# BMS_AFE_-_Cell_Inputs.net
KiCad netlist of a schematic drawn in Altium Designer
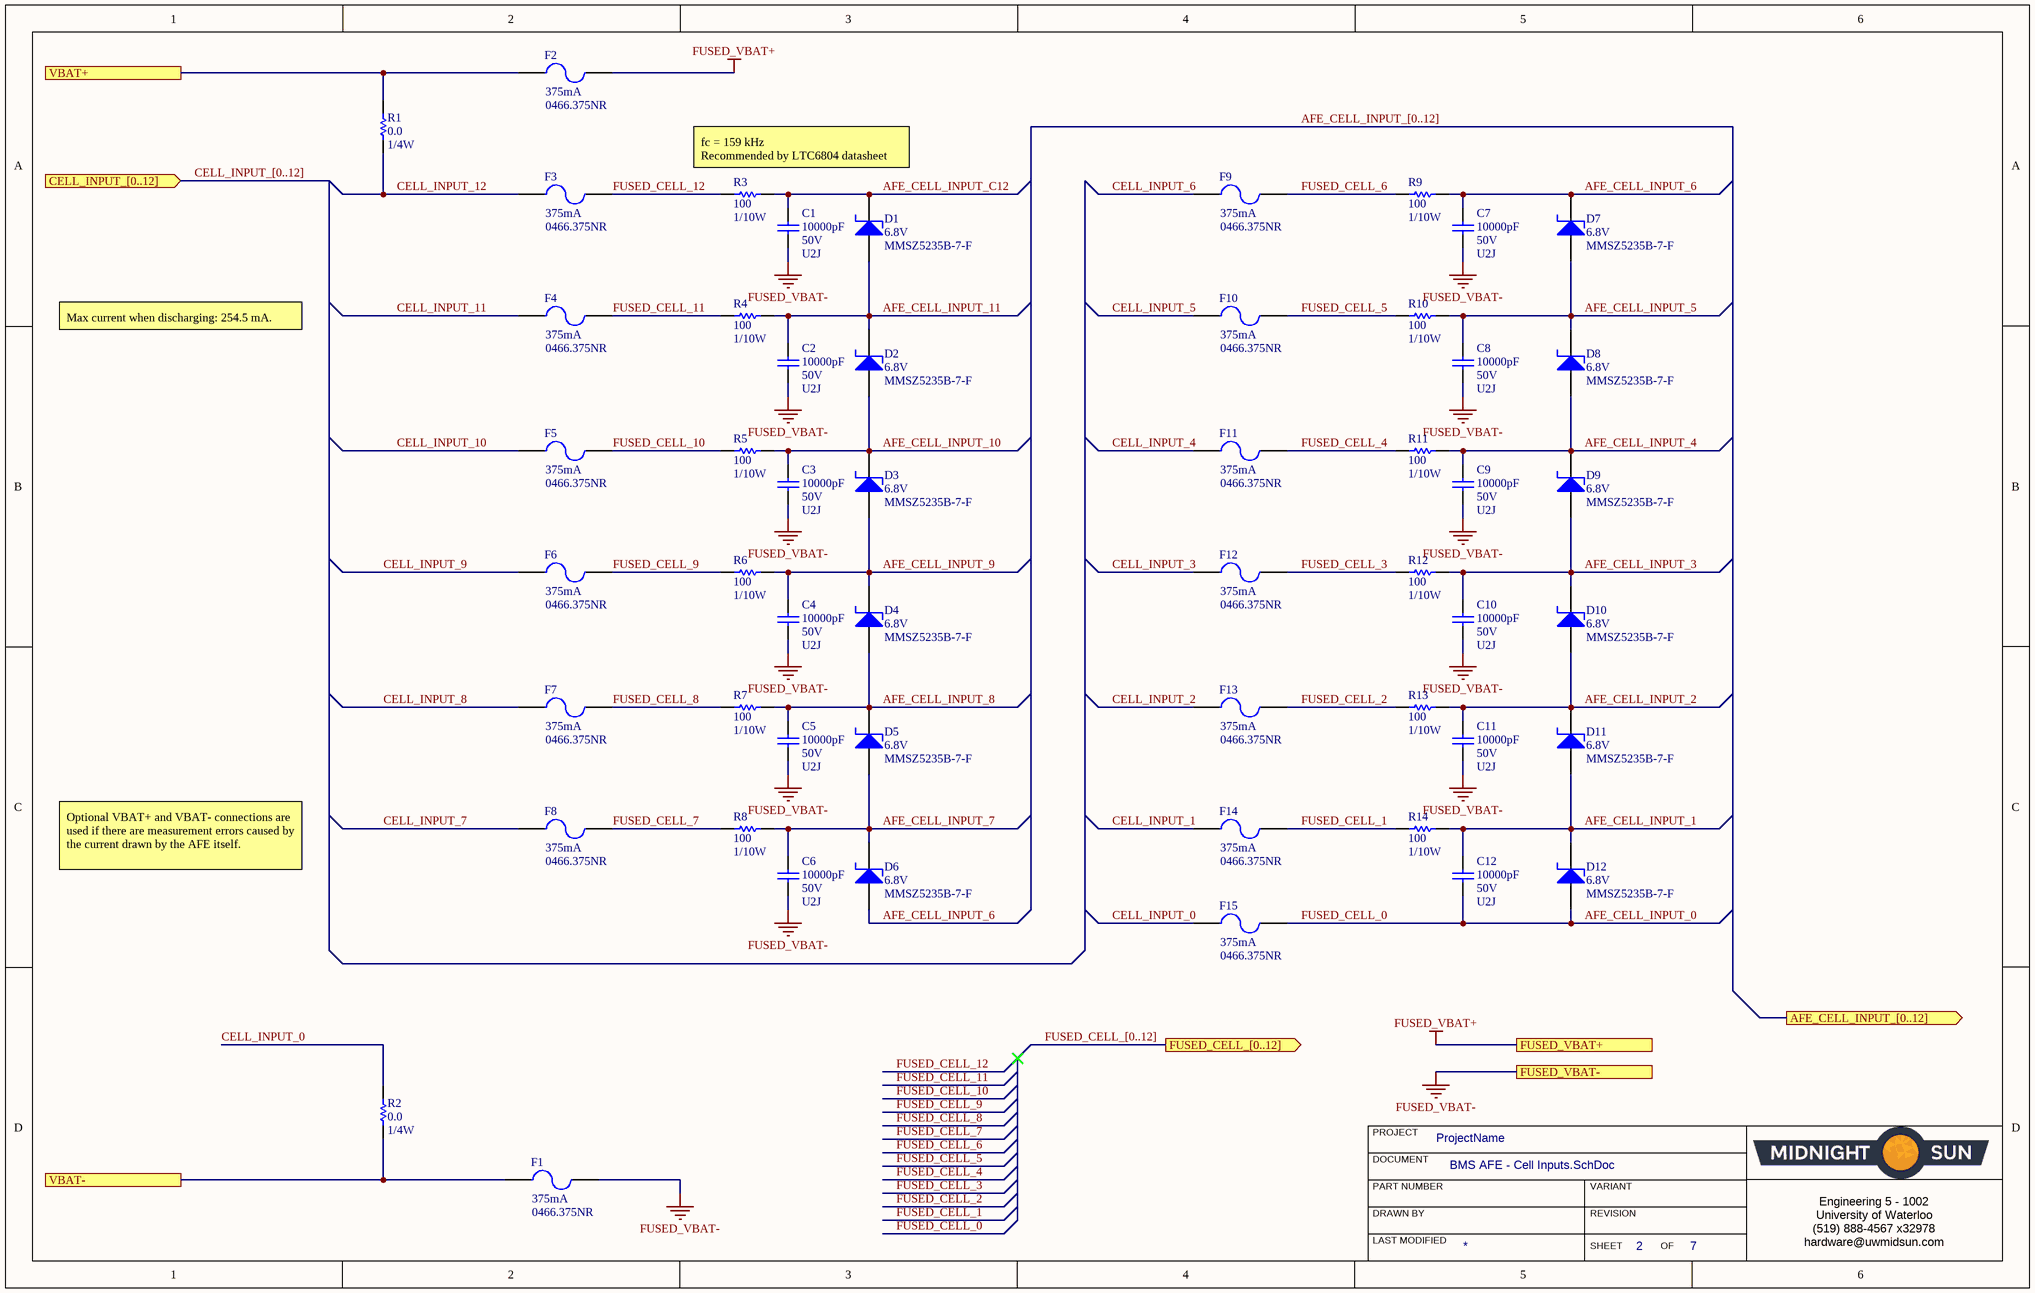
[diagram p0: BMS AFE - Cell Inputs.SchDoc]

(export (version "E")
  (design (tool "Eeschema 10.0.6"))
  (components
    (comp (ref "C1")
      (value "CAP CER 10nF 50V 5% X7R 0603")
      (footprint "CAP, 0603")
      (description "10000pF ±5% 50V Ceramic Capacitor U2J 0603 (1608 Metric)")
      (fields
        (field (name "TOLERANCE") "±5%")
        (field (name "CAPACITANCE") "10000pF")
        (field (name "VOLTAGE") "50V")
        (field (name "TEMPERATURE COEFFICIENT") "U2J")
      )
      (libsource (lib "Schematic Diagrams") (part "CAP CER 10nF 50V 5% X7R 0603"))
    )
    (comp (ref "C2")
      (value "CAP CER 10nF 50V 5% X7R 0603")
      (footprint "CAP, 0603")
      (description "10000pF ±5% 50V Ceramic Capacitor U2J 0603 (1608 Metric)")
      (fields
        (field (name "TOLERANCE") "±5%")
        (field (name "CAPACITANCE") "10000pF")
        (field (name "VOLTAGE") "50V")
        (field (name "TEMPERATURE COEFFICIENT") "U2J")
      )
      (libsource (lib "Schematic Diagrams") (part "CAP CER 10nF 50V 5% X7R 0603"))
    )
    (comp (ref "C3")
      (value "CAP CER 10nF 50V 5% X7R 0603")
      (footprint "CAP, 0603")
      (description "10000pF ±5% 50V Ceramic Capacitor U2J 0603 (1608 Metric)")
      (fields
        (field (name "TOLERANCE") "±5%")
        (field (name "CAPACITANCE") "10000pF")
        (field (name "VOLTAGE") "50V")
        (field (name "TEMPERATURE COEFFICIENT") "U2J")
      )
      (libsource (lib "Schematic Diagrams") (part "CAP CER 10nF 50V 5% X7R 0603"))
    )
    (comp (ref "C4")
      (value "CAP CER 10nF 50V 5% X7R 0603")
      (footprint "CAP, 0603")
      (description "10000pF ±5% 50V Ceramic Capacitor U2J 0603 (1608 Metric)")
      (fields
        (field (name "TOLERANCE") "±5%")
        (field (name "CAPACITANCE") "10000pF")
        (field (name "VOLTAGE") "50V")
        (field (name "TEMPERATURE COEFFICIENT") "U2J")
      )
      (libsource (lib "Schematic Diagrams") (part "CAP CER 10nF 50V 5% X7R 0603"))
    )
    (comp (ref "C5")
      (value "CAP CER 10nF 50V 5% X7R 0603")
      (footprint "CAP, 0603")
      (description "10000pF ±5% 50V Ceramic Capacitor U2J 0603 (1608 Metric)")
      (fields
        (field (name "TOLERANCE") "±5%")
        (field (name "CAPACITANCE") "10000pF")
        (field (name "VOLTAGE") "50V")
        (field (name "TEMPERATURE COEFFICIENT") "U2J")
      )
      (libsource (lib "Schematic Diagrams") (part "CAP CER 10nF 50V 5% X7R 0603"))
    )
    (comp (ref "C6")
      (value "CAP CER 10nF 50V 5% X7R 0603")
      (footprint "CAP, 0603")
      (description "10000pF ±5% 50V Ceramic Capacitor U2J 0603 (1608 Metric)")
      (fields
        (field (name "TOLERANCE") "±5%")
        (field (name "CAPACITANCE") "10000pF")
        (field (name "VOLTAGE") "50V")
        (field (name "TEMPERATURE COEFFICIENT") "U2J")
      )
      (libsource (lib "Schematic Diagrams") (part "CAP CER 10nF 50V 5% X7R 0603"))
    )
    (comp (ref "C7")
      (value "CAP CER 10nF 50V 5% X7R 0603")
      (footprint "CAP, 0603")
      (description "10000pF ±5% 50V Ceramic Capacitor U2J 0603 (1608 Metric)")
      (fields
        (field (name "TOLERANCE") "±5%")
        (field (name "CAPACITANCE") "10000pF")
        (field (name "VOLTAGE") "50V")
        (field (name "TEMPERATURE COEFFICIENT") "U2J")
      )
      (libsource (lib "Schematic Diagrams") (part "CAP CER 10nF 50V 5% X7R 0603"))
    )
    (comp (ref "C8")
      (value "CAP CER 10nF 50V 5% X7R 0603")
      (footprint "CAP, 0603")
      (description "10000pF ±5% 50V Ceramic Capacitor U2J 0603 (1608 Metric)")
      (fields
        (field (name "TOLERANCE") "±5%")
        (field (name "CAPACITANCE") "10000pF")
        (field (name "VOLTAGE") "50V")
        (field (name "TEMPERATURE COEFFICIENT") "U2J")
      )
      (libsource (lib "Schematic Diagrams") (part "CAP CER 10nF 50V 5% X7R 0603"))
    )
    (comp (ref "C9")
      (value "CAP CER 10nF 50V 5% X7R 0603")
      (footprint "CAP, 0603")
      (description "10000pF ±5% 50V Ceramic Capacitor U2J 0603 (1608 Metric)")
      (fields
        (field (name "TOLERANCE") "±5%")
        (field (name "CAPACITANCE") "10000pF")
        (field (name "VOLTAGE") "50V")
        (field (name "TEMPERATURE COEFFICIENT") "U2J")
      )
      (libsource (lib "Schematic Diagrams") (part "CAP CER 10nF 50V 5% X7R 0603"))
    )
    (comp (ref "C10")
      (value "CAP CER 10nF 50V 5% X7R 0603")
      (footprint "CAP, 0603")
      (description "10000pF ±5% 50V Ceramic Capacitor U2J 0603 (1608 Metric)")
      (fields
        (field (name "TOLERANCE") "±5%")
        (field (name "CAPACITANCE") "10000pF")
        (field (name "VOLTAGE") "50V")
        (field (name "TEMPERATURE COEFFICIENT") "U2J")
      )
      (libsource (lib "Schematic Diagrams") (part "CAP CER 10nF 50V 5% X7R 0603"))
    )
    (comp (ref "C11")
      (value "CAP CER 10nF 50V 5% X7R 0603")
      (footprint "CAP, 0603")
      (description "10000pF ±5% 50V Ceramic Capacitor U2J 0603 (1608 Metric)")
      (fields
        (field (name "TOLERANCE") "±5%")
        (field (name "CAPACITANCE") "10000pF")
        (field (name "VOLTAGE") "50V")
        (field (name "TEMPERATURE COEFFICIENT") "U2J")
      )
      (libsource (lib "Schematic Diagrams") (part "CAP CER 10nF 50V 5% X7R 0603"))
    )
    (comp (ref "C12")
      (value "CAP CER 10nF 50V 5% X7R 0603")
      (footprint "CAP, 0603")
      (description "10000pF ±5% 50V Ceramic Capacitor U2J 0603 (1608 Metric)")
      (fields
        (field (name "TOLERANCE") "±5%")
        (field (name "CAPACITANCE") "10000pF")
        (field (name "VOLTAGE") "50V")
        (field (name "TEMPERATURE COEFFICIENT") "U2J")
      )
      (libsource (lib "Schematic Diagrams") (part "CAP CER 10nF 50V 5% X7R 0603"))
    )
    (comp (ref "D1")
      (value "6.8V")
      (footprint "DIODE SOD123")
      (description "Zener Diode 6.8V 500mW ±5% Surface Mount SOD-123")
      (fields
        (field (name "MANUFACTURER") "Diodes Incorporated")
        (field (name "TOLERANCE") "±5%")
        (field (name "MANUFACTURER PART NUMBER") "MMSZ5235B-7-F")
      )
      (libsource (lib "Schematic Diagrams") (part "DIODE ZENER 6.8V 500MW SOD123"))
    )
    (comp (ref "D2")
      (value "6.8V")
      (footprint "DIODE SOD123")
      (description "Zener Diode 6.8V 500mW ±5% Surface Mount SOD-123")
      (fields
        (field (name "MANUFACTURER") "Diodes Incorporated")
        (field (name "TOLERANCE") "±5%")
        (field (name "MANUFACTURER PART NUMBER") "MMSZ5235B-7-F")
      )
      (libsource (lib "Schematic Diagrams") (part "DIODE ZENER 6.8V 500MW SOD123"))
    )
    (comp (ref "D3")
      (value "6.8V")
      (footprint "DIODE SOD123")
      (description "Zener Diode 6.8V 500mW ±5% Surface Mount SOD-123")
      (fields
        (field (name "MANUFACTURER") "Diodes Incorporated")
        (field (name "TOLERANCE") "±5%")
        (field (name "MANUFACTURER PART NUMBER") "MMSZ5235B-7-F")
      )
      (libsource (lib "Schematic Diagrams") (part "DIODE ZENER 6.8V 500MW SOD123"))
    )
    (comp (ref "D4")
      (value "6.8V")
      (footprint "DIODE SOD123")
      (description "Zener Diode 6.8V 500mW ±5% Surface Mount SOD-123")
      (fields
        (field (name "MANUFACTURER") "Diodes Incorporated")
        (field (name "TOLERANCE") "±5%")
        (field (name "MANUFACTURER PART NUMBER") "MMSZ5235B-7-F")
      )
      (libsource (lib "Schematic Diagrams") (part "DIODE ZENER 6.8V 500MW SOD123"))
    )
    (comp (ref "D5")
      (value "6.8V")
      (footprint "DIODE SOD123")
      (description "Zener Diode 6.8V 500mW ±5% Surface Mount SOD-123")
      (fields
        (field (name "MANUFACTURER") "Diodes Incorporated")
        (field (name "TOLERANCE") "±5%")
        (field (name "MANUFACTURER PART NUMBER") "MMSZ5235B-7-F")
      )
      (libsource (lib "Schematic Diagrams") (part "DIODE ZENER 6.8V 500MW SOD123"))
    )
    (comp (ref "D6")
      (value "6.8V")
      (footprint "DIODE SOD123")
      (description "Zener Diode 6.8V 500mW ±5% Surface Mount SOD-123")
      (fields
        (field (name "MANUFACTURER") "Diodes Incorporated")
        (field (name "TOLERANCE") "±5%")
        (field (name "MANUFACTURER PART NUMBER") "MMSZ5235B-7-F")
      )
      (libsource (lib "Schematic Diagrams") (part "DIODE ZENER 6.8V 500MW SOD123"))
    )
    (comp (ref "D7")
      (value "6.8V")
      (footprint "DIODE SOD123")
      (description "Zener Diode 6.8V 500mW ±5% Surface Mount SOD-123")
      (fields
        (field (name "MANUFACTURER") "Diodes Incorporated")
        (field (name "TOLERANCE") "±5%")
        (field (name "MANUFACTURER PART NUMBER") "MMSZ5235B-7-F")
      )
      (libsource (lib "Schematic Diagrams") (part "DIODE ZENER 6.8V 500MW SOD123"))
    )
    (comp (ref "D8")
      (value "6.8V")
      (footprint "DIODE SOD123")
      (description "Zener Diode 6.8V 500mW ±5% Surface Mount SOD-123")
      (fields
        (field (name "MANUFACTURER") "Diodes Incorporated")
        (field (name "TOLERANCE") "±5%")
        (field (name "MANUFACTURER PART NUMBER") "MMSZ5235B-7-F")
      )
      (libsource (lib "Schematic Diagrams") (part "DIODE ZENER 6.8V 500MW SOD123"))
    )
    (comp (ref "D9")
      (value "6.8V")
      (footprint "DIODE SOD123")
      (description "Zener Diode 6.8V 500mW ±5% Surface Mount SOD-123")
      (fields
        (field (name "MANUFACTURER") "Diodes Incorporated")
        (field (name "TOLERANCE") "±5%")
        (field (name "MANUFACTURER PART NUMBER") "MMSZ5235B-7-F")
      )
      (libsource (lib "Schematic Diagrams") (part "DIODE ZENER 6.8V 500MW SOD123"))
    )
    (comp (ref "D10")
      (value "6.8V")
      (footprint "DIODE SOD123")
      (description "Zener Diode 6.8V 500mW ±5% Surface Mount SOD-123")
      (fields
        (field (name "MANUFACTURER") "Diodes Incorporated")
        (field (name "TOLERANCE") "±5%")
        (field (name "MANUFACTURER PART NUMBER") "MMSZ5235B-7-F")
      )
      (libsource (lib "Schematic Diagrams") (part "DIODE ZENER 6.8V 500MW SOD123"))
    )
    (comp (ref "D11")
      (value "6.8V")
      (footprint "DIODE SOD123")
      (description "Zener Diode 6.8V 500mW ±5% Surface Mount SOD-123")
      (fields
        (field (name "MANUFACTURER") "Diodes Incorporated")
        (field (name "TOLERANCE") "±5%")
        (field (name "MANUFACTURER PART NUMBER") "MMSZ5235B-7-F")
      )
      (libsource (lib "Schematic Diagrams") (part "DIODE ZENER 6.8V 500MW SOD123"))
    )
    (comp (ref "D12")
      (value "6.8V")
      (footprint "DIODE SOD123")
      (description "Zener Diode 6.8V 500mW ±5% Surface Mount SOD-123")
      (fields
        (field (name "MANUFACTURER") "Diodes Incorporated")
        (field (name "TOLERANCE") "±5%")
        (field (name "MANUFACTURER PART NUMBER") "MMSZ5235B-7-F")
      )
      (libsource (lib "Schematic Diagrams") (part "DIODE ZENER 6.8V 500MW SOD123"))
    )
    (comp (ref "F1")
      (value "375 mA")
      (footprint "FUSE LITTLEFUSE 0466 1206")
      (description "FUSE BOARD MNT 375MA 125VAC/VDC")
      (fields
        (field (name "MANUFACTURER") "Littelfuse")
        (field (name "MANUFACTURER PART NUMBER") "0466.375NR")
        (field (name "CURRENT RATING") "375mA")
      )
      (libsource (lib "Schematic Diagrams") (part "FUSE 375MA 125VDC 1206"))
    )
    (comp (ref "F2")
      (value "375 mA")
      (footprint "FUSE LITTLEFUSE 0466 1206")
      (description "FUSE BOARD MNT 375MA 125VAC/VDC")
      (fields
        (field (name "MANUFACTURER") "Littelfuse")
        (field (name "MANUFACTURER PART NUMBER") "0466.375NR")
        (field (name "CURRENT RATING") "375mA")
      )
      (libsource (lib "Schematic Diagrams") (part "FUSE 375MA 125VDC 1206"))
    )
    (comp (ref "F3")
      (value "375 mA")
      (footprint "FUSE LITTLEFUSE 0466 1206")
      (description "FUSE BOARD MNT 375MA 125VAC/VDC")
      (fields
        (field (name "MANUFACTURER") "Littelfuse")
        (field (name "MANUFACTURER PART NUMBER") "0466.375NR")
        (field (name "CURRENT RATING") "375mA")
      )
      (libsource (lib "Schematic Diagrams") (part "FUSE 375MA 125VDC 1206"))
    )
    (comp (ref "F4")
      (value "375 mA")
      (footprint "FUSE LITTLEFUSE 0466 1206")
      (description "FUSE BOARD MNT 375MA 125VAC/VDC")
      (fields
        (field (name "MANUFACTURER") "Littelfuse")
        (field (name "MANUFACTURER PART NUMBER") "0466.375NR")
        (field (name "CURRENT RATING") "375mA")
      )
      (libsource (lib "Schematic Diagrams") (part "FUSE 375MA 125VDC 1206"))
    )
    (comp (ref "F5")
      (value "375 mA")
      (footprint "FUSE LITTLEFUSE 0466 1206")
      (description "FUSE BOARD MNT 375MA 125VAC/VDC")
      (fields
        (field (name "MANUFACTURER") "Littelfuse")
        (field (name "MANUFACTURER PART NUMBER") "0466.375NR")
        (field (name "CURRENT RATING") "375mA")
      )
      (libsource (lib "Schematic Diagrams") (part "FUSE 375MA 125VDC 1206"))
    )
    (comp (ref "F6")
      (value "375 mA")
      (footprint "FUSE LITTLEFUSE 0466 1206")
      (description "FUSE BOARD MNT 375MA 125VAC/VDC")
      (fields
        (field (name "MANUFACTURER") "Littelfuse")
        (field (name "MANUFACTURER PART NUMBER") "0466.375NR")
        (field (name "CURRENT RATING") "375mA")
      )
      (libsource (lib "Schematic Diagrams") (part "FUSE 375MA 125VDC 1206"))
    )
    (comp (ref "F7")
      (value "375 mA")
      (footprint "FUSE LITTLEFUSE 0466 1206")
      (description "FUSE BOARD MNT 375MA 125VAC/VDC")
      (fields
        (field (name "MANUFACTURER") "Littelfuse")
        (field (name "MANUFACTURER PART NUMBER") "0466.375NR")
        (field (name "CURRENT RATING") "375mA")
      )
      (libsource (lib "Schematic Diagrams") (part "FUSE 375MA 125VDC 1206"))
    )
    (comp (ref "F8")
      (value "375 mA")
      (footprint "FUSE LITTLEFUSE 0466 1206")
      (description "FUSE BOARD MNT 375MA 125VAC/VDC")
      (fields
        (field (name "MANUFACTURER") "Littelfuse")
        (field (name "MANUFACTURER PART NUMBER") "0466.375NR")
        (field (name "CURRENT RATING") "375mA")
      )
      (libsource (lib "Schematic Diagrams") (part "FUSE 375MA 125VDC 1206"))
    )
    (comp (ref "F9")
      (value "375 mA")
      (footprint "FUSE LITTLEFUSE 0466 1206")
      (description "FUSE BOARD MNT 375MA 125VAC/VDC")
      (fields
        (field (name "MANUFACTURER") "Littelfuse")
        (field (name "MANUFACTURER PART NUMBER") "0466.375NR")
        (field (name "CURRENT RATING") "375mA")
      )
      (libsource (lib "Schematic Diagrams") (part "FUSE 375MA 125VDC 1206"))
    )
    (comp (ref "F10")
      (value "375 mA")
      (footprint "FUSE LITTLEFUSE 0466 1206")
      (description "FUSE BOARD MNT 375MA 125VAC/VDC")
      (fields
        (field (name "MANUFACTURER") "Littelfuse")
        (field (name "MANUFACTURER PART NUMBER") "0466.375NR")
        (field (name "CURRENT RATING") "375mA")
      )
      (libsource (lib "Schematic Diagrams") (part "FUSE 375MA 125VDC 1206"))
    )
    (comp (ref "F11")
      (value "375 mA")
      (footprint "FUSE LITTLEFUSE 0466 1206")
      (description "FUSE BOARD MNT 375MA 125VAC/VDC")
      (fields
        (field (name "MANUFACTURER") "Littelfuse")
        (field (name "MANUFACTURER PART NUMBER") "0466.375NR")
        (field (name "CURRENT RATING") "375mA")
      )
      (libsource (lib "Schematic Diagrams") (part "FUSE 375MA 125VDC 1206"))
    )
    (comp (ref "F12")
      (value "375 mA")
      (footprint "FUSE LITTLEFUSE 0466 1206")
      (description "FUSE BOARD MNT 375MA 125VAC/VDC")
      (fields
        (field (name "MANUFACTURER") "Littelfuse")
        (field (name "MANUFACTURER PART NUMBER") "0466.375NR")
        (field (name "CURRENT RATING") "375mA")
      )
      (libsource (lib "Schematic Diagrams") (part "FUSE 375MA 125VDC 1206"))
    )
    (comp (ref "F13")
      (value "375 mA")
      (footprint "FUSE LITTLEFUSE 0466 1206")
      (description "FUSE BOARD MNT 375MA 125VAC/VDC")
      (fields
        (field (name "MANUFACTURER") "Littelfuse")
        (field (name "MANUFACTURER PART NUMBER") "0466.375NR")
        (field (name "CURRENT RATING") "375mA")
      )
      (libsource (lib "Schematic Diagrams") (part "FUSE 375MA 125VDC 1206"))
    )
    (comp (ref "F14")
      (value "375 mA")
      (footprint "FUSE LITTLEFUSE 0466 1206")
      (description "FUSE BOARD MNT 375MA 125VAC/VDC")
      (fields
        (field (name "MANUFACTURER") "Littelfuse")
        (field (name "MANUFACTURER PART NUMBER") "0466.375NR")
        (field (name "CURRENT RATING") "375mA")
      )
      (libsource (lib "Schematic Diagrams") (part "FUSE 375MA 125VDC 1206"))
    )
    (comp (ref "F15")
      (value "375 mA")
      (footprint "FUSE LITTLEFUSE 0466 1206")
      (description "FUSE BOARD MNT 375MA 125VAC/VDC")
      (fields
        (field (name "MANUFACTURER") "Littelfuse")
        (field (name "MANUFACTURER PART NUMBER") "0466.375NR")
        (field (name "CURRENT RATING") "375mA")
      )
      (libsource (lib "Schematic Diagrams") (part "FUSE 375MA 125VDC 1206"))
    )
    (comp (ref "R1")
      (value "RES 0.0 OHM 1/4W 0603")
      (footprint "RES, 0603")
      (description "RES SMD 0.0 OHM JUMPER 1/4W 0603")
      (fields (field (name "RESISTANCE") "0.0") (field (name "POWER (WATTS)") "1/4W"))
      (libsource (lib "Schematic Diagrams") (part "RES 0.0 OHM 1/4W 0603"))
    )
    (comp (ref "R2")
      (value "RES 0.0 OHM 1/4W 0603")
      (footprint "RES, 0603")
      (description "RES SMD 0.0 OHM JUMPER 1/4W 0603")
      (fields (field (name "RESISTANCE") "0.0") (field (name "POWER (WATTS)") "1/4W"))
      (libsource (lib "Schematic Diagrams") (part "RES 0.0 OHM 1/4W 0603"))
    )
    (comp (ref "R3")
      (value "RES 100 OHM 1% 1/10W 0603")
      (footprint "RES, 0603")
      (description "100 Ohm ±1% 0.1W, 1/10W Chip Resistor 0603 (1608 Metric) Moisture Resistant Thick Film")
      (fields
        (field (name "TOLERANCE") "±1%")
        (field (name "RESISTANCE") "100")
        (field (name "POWER") "1/10W")
      )
      (libsource (lib "Schematic Diagrams") (part "RES 100 OHM 1% 1/10W 0603"))
    )
    (comp (ref "R4")
      (value "RES 100 OHM 1% 1/10W 0603")
      (footprint "RES, 0603")
      (description "100 Ohm ±1% 0.1W, 1/10W Chip Resistor 0603 (1608 Metric) Moisture Resistant Thick Film")
      (fields
        (field (name "TOLERANCE") "±1%")
        (field (name "RESISTANCE") "100")
        (field (name "POWER") "1/10W")
      )
      (libsource (lib "Schematic Diagrams") (part "RES 100 OHM 1% 1/10W 0603"))
    )
    (comp (ref "R5")
      (value "RES 100 OHM 1% 1/10W 0603")
      (footprint "RES, 0603")
      (description "100 Ohm ±1% 0.1W, 1/10W Chip Resistor 0603 (1608 Metric) Moisture Resistant Thick Film")
      (fields
        (field (name "TOLERANCE") "±1%")
        (field (name "RESISTANCE") "100")
        (field (name "POWER") "1/10W")
      )
      (libsource (lib "Schematic Diagrams") (part "RES 100 OHM 1% 1/10W 0603"))
    )
    (comp (ref "R6")
      (value "RES 100 OHM 1% 1/10W 0603")
      (footprint "RES, 0603")
      (description "100 Ohm ±1% 0.1W, 1/10W Chip Resistor 0603 (1608 Metric) Moisture Resistant Thick Film")
      (fields
        (field (name "TOLERANCE") "±1%")
        (field (name "RESISTANCE") "100")
        (field (name "POWER") "1/10W")
      )
      (libsource (lib "Schematic Diagrams") (part "RES 100 OHM 1% 1/10W 0603"))
    )
    (comp (ref "R7")
      (value "RES 100 OHM 1% 1/10W 0603")
      (footprint "RES, 0603")
      (description "100 Ohm ±1% 0.1W, 1/10W Chip Resistor 0603 (1608 Metric) Moisture Resistant Thick Film")
      (fields
        (field (name "TOLERANCE") "±1%")
        (field (name "RESISTANCE") "100")
        (field (name "POWER") "1/10W")
      )
      (libsource (lib "Schematic Diagrams") (part "RES 100 OHM 1% 1/10W 0603"))
    )
    (comp (ref "R8")
      (value "RES 100 OHM 1% 1/10W 0603")
      (footprint "RES, 0603")
      (description "100 Ohm ±1% 0.1W, 1/10W Chip Resistor 0603 (1608 Metric) Moisture Resistant Thick Film")
      (fields
        (field (name "TOLERANCE") "±1%")
        (field (name "RESISTANCE") "100")
        (field (name "POWER") "1/10W")
      )
      (libsource (lib "Schematic Diagrams") (part "RES 100 OHM 1% 1/10W 0603"))
    )
    (comp (ref "R9")
      (value "RES 100 OHM 1% 1/10W 0603")
      (footprint "RES, 0603")
      (description "100 Ohm ±1% 0.1W, 1/10W Chip Resistor 0603 (1608 Metric) Moisture Resistant Thick Film")
      (fields
        (field (name "TOLERANCE") "±1%")
        (field (name "RESISTANCE") "100")
        (field (name "POWER") "1/10W")
      )
      (libsource (lib "Schematic Diagrams") (part "RES 100 OHM 1% 1/10W 0603"))
    )
    (comp (ref "R10")
      (value "RES 100 OHM 1% 1/10W 0603")
      (footprint "RES, 0603")
      (description "100 Ohm ±1% 0.1W, 1/10W Chip Resistor 0603 (1608 Metric) Moisture Resistant Thick Film")
      (fields
        (field (name "TOLERANCE") "±1%")
        (field (name "RESISTANCE") "100")
        (field (name "POWER") "1/10W")
      )
      (libsource (lib "Schematic Diagrams") (part "RES 100 OHM 1% 1/10W 0603"))
    )
    (comp (ref "R11")
      (value "RES 100 OHM 1% 1/10W 0603")
      (footprint "RES, 0603")
      (description "100 Ohm ±1% 0.1W, 1/10W Chip Resistor 0603 (1608 Metric) Moisture Resistant Thick Film")
      (fields
        (field (name "TOLERANCE") "±1%")
        (field (name "RESISTANCE") "100")
        (field (name "POWER") "1/10W")
      )
      (libsource (lib "Schematic Diagrams") (part "RES 100 OHM 1% 1/10W 0603"))
    )
    (comp (ref "R12")
      (value "RES 100 OHM 1% 1/10W 0603")
      (footprint "RES, 0603")
      (description "100 Ohm ±1% 0.1W, 1/10W Chip Resistor 0603 (1608 Metric) Moisture Resistant Thick Film")
      (fields
        (field (name "TOLERANCE") "±1%")
        (field (name "RESISTANCE") "100")
        (field (name "POWER") "1/10W")
      )
      (libsource (lib "Schematic Diagrams") (part "RES 100 OHM 1% 1/10W 0603"))
    )
    (comp (ref "R13")
      (value "RES 100 OHM 1% 1/10W 0603")
      (footprint "RES, 0603")
      (description "100 Ohm ±1% 0.1W, 1/10W Chip Resistor 0603 (1608 Metric) Moisture Resistant Thick Film")
      (fields
        (field (name "TOLERANCE") "±1%")
        (field (name "RESISTANCE") "100")
        (field (name "POWER") "1/10W")
      )
      (libsource (lib "Schematic Diagrams") (part "RES 100 OHM 1% 1/10W 0603"))
    )
    (comp (ref "R14")
      (value "RES 100 OHM 1% 1/10W 0603")
      (footprint "RES, 0603")
      (description "100 Ohm ±1% 0.1W, 1/10W Chip Resistor 0603 (1608 Metric) Moisture Resistant Thick Film")
      (fields
        (field (name "TOLERANCE") "±1%")
        (field (name "RESISTANCE") "100")
        (field (name "POWER") "1/10W")
      )
      (libsource (lib "Schematic Diagrams") (part "RES 100 OHM 1% 1/10W 0603"))
    )
  )
  (nets
    (net (code "2") (name "/AFE_CELL_INPUT_1") (class "Default")
      (node (ref "C12") (pin "1") (pinfunction "1_1") (pintype "passive"))
      (node (ref "D11") (pin "2") (pinfunction "A_2") (pintype "passive"))
      (node (ref "D12") (pin "1") (pinfunction "K_1") (pintype "passive"))
      (node (ref "R14") (pin "2") (pinfunction "2_2") (pintype "passive"))
    )
    (net (code "3") (name "/AFE_CELL_INPUT_2") (class "Default")
      (node (ref "C11") (pin "1") (pinfunction "1_1") (pintype "passive"))
      (node (ref "D10") (pin "2") (pinfunction "A_2") (pintype "passive"))
      (node (ref "D11") (pin "1") (pinfunction "K_1") (pintype "passive"))
      (node (ref "R13") (pin "2") (pinfunction "2_2") (pintype "passive"))
    )
    (net (code "4") (name "/AFE_CELL_INPUT_3") (class "Default")
      (node (ref "C10") (pin "1") (pinfunction "1_1") (pintype "passive"))
      (node (ref "D10") (pin "1") (pinfunction "K_1") (pintype "passive"))
      (node (ref "D9") (pin "2") (pinfunction "A_2") (pintype "passive"))
      (node (ref "R12") (pin "2") (pinfunction "2_2") (pintype "passive"))
    )
    (net (code "5") (name "/AFE_CELL_INPUT_4") (class "Default")
      (node (ref "C9") (pin "1") (pinfunction "1_1") (pintype "passive"))
      (node (ref "D8") (pin "2") (pinfunction "A_2") (pintype "passive"))
      (node (ref "D9") (pin "1") (pinfunction "K_1") (pintype "passive"))
      (node (ref "R11") (pin "2") (pinfunction "2_2") (pintype "passive"))
    )
    (net (code "6") (name "/AFE_CELL_INPUT_5") (class "Default")
      (node (ref "C8") (pin "1") (pinfunction "1_1") (pintype "passive"))
      (node (ref "D7") (pin "2") (pinfunction "A_2") (pintype "passive"))
      (node (ref "D8") (pin "1") (pinfunction "K_1") (pintype "passive"))
      (node (ref "R10") (pin "2") (pinfunction "2_2") (pintype "passive"))
    )
    (net (code "7") (name "/AFE_CELL_INPUT_6") (class "Default")
      (node (ref "C7") (pin "1") (pinfunction "1_1") (pintype "passive"))
      (node (ref "D6") (pin "2") (pinfunction "A_2") (pintype "passive"))
      (node (ref "D7") (pin "1") (pinfunction "K_1") (pintype "passive"))
      (node (ref "R9") (pin "2") (pinfunction "2_2") (pintype "passive"))
    )
    (net (code "8") (name "/AFE_CELL_INPUT_7") (class "Default")
      (node (ref "C6") (pin "1") (pinfunction "1_1") (pintype "passive"))
      (node (ref "D5") (pin "2") (pinfunction "A_2") (pintype "passive"))
      (node (ref "D6") (pin "1") (pinfunction "K_1") (pintype "passive"))
      (node (ref "R8") (pin "2") (pinfunction "2_2") (pintype "passive"))
    )
    (net (code "9") (name "/AFE_CELL_INPUT_8") (class "Default")
      (node (ref "C5") (pin "1") (pinfunction "1_1") (pintype "passive"))
      (node (ref "D4") (pin "2") (pinfunction "A_2") (pintype "passive"))
      (node (ref "D5") (pin "1") (pinfunction "K_1") (pintype "passive"))
      (node (ref "R7") (pin "2") (pinfunction "2_2") (pintype "passive"))
    )
    (net (code "10") (name "/AFE_CELL_INPUT_9") (class "Default")
      (node (ref "C4") (pin "1") (pinfunction "1_1") (pintype "passive"))
      (node (ref "D3") (pin "2") (pinfunction "A_2") (pintype "passive"))
      (node (ref "D4") (pin "1") (pinfunction "K_1") (pintype "passive"))
      (node (ref "R6") (pin "2") (pinfunction "2_2") (pintype "passive"))
    )
    (net (code "11") (name "/AFE_CELL_INPUT_10") (class "Default")
      (node (ref "C3") (pin "1") (pinfunction "1_1") (pintype "passive"))
      (node (ref "D2") (pin "2") (pinfunction "A_2") (pintype "passive"))
      (node (ref "D3") (pin "1") (pinfunction "K_1") (pintype "passive"))
      (node (ref "R5") (pin "2") (pinfunction "2_2") (pintype "passive"))
    )
    (net (code "12") (name "/AFE_CELL_INPUT_11") (class "Default")
      (node (ref "C2") (pin "1") (pinfunction "1_1") (pintype "passive"))
      (node (ref "D1") (pin "2") (pinfunction "A_2") (pintype "passive"))
      (node (ref "D2") (pin "1") (pinfunction "K_1") (pintype "passive"))
      (node (ref "R4") (pin "2") (pinfunction "2_2") (pintype "passive"))
    )
    (net (code "13") (name "/AFE_CELL_INPUT_C12") (class "Default")
      (node (ref "C1") (pin "1") (pinfunction "1_1") (pintype "passive"))
      (node (ref "D1") (pin "1") (pinfunction "K_1") (pintype "passive"))
      (node (ref "R3") (pin "2") (pinfunction "2_2") (pintype "passive"))
    )
    (net (code "15") (name "/CELL_INPUT_0") (class "Default")
      (node (ref "F15") (pin "1") (pinfunction "1_1") (pintype "passive"))
      (node (ref "R2") (pin "1") (pinfunction "1_1") (pintype "passive"))
    )
    (net (code "16") (name "/CELL_INPUT_1") (class "Default")
      (node (ref "F14") (pin "1") (pinfunction "1_1") (pintype "passive"))
    )
    (net (code "17") (name "/CELL_INPUT_2") (class "Default")
      (node (ref "F13") (pin "1") (pinfunction "1_1") (pintype "passive"))
    )
    (net (code "18") (name "/CELL_INPUT_3") (class "Default")
      (node (ref "F12") (pin "1") (pinfunction "1_1") (pintype "passive"))
    )
    (net (code "19") (name "/CELL_INPUT_4") (class "Default")
      (node (ref "F11") (pin "1") (pinfunction "1_1") (pintype "passive"))
    )
    (net (code "20") (name "/CELL_INPUT_5") (class "Default")
      (node (ref "F10") (pin "1") (pinfunction "1_1") (pintype "passive"))
    )
    (net (code "21") (name "/CELL_INPUT_6") (class "Default")
      (node (ref "F9") (pin "1") (pinfunction "1_1") (pintype "passive"))
    )
    (net (code "22") (name "/CELL_INPUT_7") (class "Default")
      (node (ref "F8") (pin "1") (pinfunction "1_1") (pintype "passive"))
    )
    (net (code "23") (name "/CELL_INPUT_8") (class "Default")
      (node (ref "F7") (pin "1") (pinfunction "1_1") (pintype "passive"))
    )
    (net (code "24") (name "/CELL_INPUT_9") (class "Default")
      (node (ref "F6") (pin "1") (pinfunction "1_1") (pintype "passive"))
    )
    (net (code "25") (name "/CELL_INPUT_10") (class "Default")
      (node (ref "F5") (pin "1") (pinfunction "1_1") (pintype "passive"))
    )
    (net (code "26") (name "/CELL_INPUT_11") (class "Default")
      (node (ref "F4") (pin "1") (pinfunction "1_1") (pintype "passive"))
    )
    (net (code "27") (name "/CELL_INPUT_12") (class "Default")
      (node (ref "F3") (pin "1") (pinfunction "1_1") (pintype "passive"))
      (node (ref "R1") (pin "2") (pinfunction "2_2") (pintype "passive"))
    )
    (net (code "29") (name "/FUSED_CELL_0") (class "Default")
      (node (ref "C12") (pin "2") (pinfunction "2_2") (pintype "passive"))
      (node (ref "D12") (pin "2") (pinfunction "A_2") (pintype "passive"))
      (node (ref "F15") (pin "2") (pinfunction "2_2") (pintype "passive"))
    )
    (net (code "30") (name "/FUSED_CELL_1") (class "Default")
      (node (ref "F14") (pin "2") (pinfunction "2_2") (pintype "passive"))
      (node (ref "R14") (pin "1") (pinfunction "1_1") (pintype "passive"))
    )
    (net (code "31") (name "/FUSED_CELL_2") (class "Default")
      (node (ref "F13") (pin "2") (pinfunction "2_2") (pintype "passive"))
      (node (ref "R13") (pin "1") (pinfunction "1_1") (pintype "passive"))
    )
    (net (code "32") (name "/FUSED_CELL_3") (class "Default")
      (node (ref "F12") (pin "2") (pinfunction "2_2") (pintype "passive"))
      (node (ref "R12") (pin "1") (pinfunction "1_1") (pintype "passive"))
    )
    (net (code "33") (name "/FUSED_CELL_4") (class "Default")
      (node (ref "F11") (pin "2") (pinfunction "2_2") (pintype "passive"))
      (node (ref "R11") (pin "1") (pinfunction "1_1") (pintype "passive"))
    )
    (net (code "34") (name "/FUSED_CELL_5") (class "Default")
      (node (ref "F10") (pin "2") (pinfunction "2_2") (pintype "passive"))
      (node (ref "R10") (pin "1") (pinfunction "1_1") (pintype "passive"))
    )
    (net (code "35") (name "/FUSED_CELL_6") (class "Default")
      (node (ref "F9") (pin "2") (pinfunction "2_2") (pintype "passive"))
      (node (ref "R9") (pin "1") (pinfunction "1_1") (pintype "passive"))
    )
    (net (code "36") (name "/FUSED_CELL_7") (class "Default")
      (node (ref "F8") (pin "2") (pinfunction "2_2") (pintype "passive"))
      (node (ref "R8") (pin "1") (pinfunction "1_1") (pintype "passive"))
    )
    (net (code "37") (name "/FUSED_CELL_8") (class "Default")
      (node (ref "F7") (pin "2") (pinfunction "2_2") (pintype "passive"))
      (node (ref "R7") (pin "1") (pinfunction "1_1") (pintype "passive"))
    )
    (net (code "38") (name "/FUSED_CELL_9") (class "Default")
      (node (ref "F6") (pin "2") (pinfunction "2_2") (pintype "passive"))
      (node (ref "R6") (pin "1") (pinfunction "1_1") (pintype "passive"))
    )
    (net (code "39") (name "/FUSED_CELL_10") (class "Default")
      (node (ref "F5") (pin "2") (pinfunction "2_2") (pintype "passive"))
      (node (ref "R5") (pin "1") (pinfunction "1_1") (pintype "passive"))
    )
    (net (code "40") (name "/FUSED_CELL_11") (class "Default")
      (node (ref "F4") (pin "2") (pinfunction "2_2") (pintype "passive"))
      (node (ref "R4") (pin "1") (pinfunction "1_1") (pintype "passive"))
    )
    (net (code "41") (name "/FUSED_CELL_12") (class "Default")
      (node (ref "F3") (pin "2") (pinfunction "2_2") (pintype "passive"))
      (node (ref "R3") (pin "1") (pinfunction "1_1") (pintype "passive"))
    )
    (net (code "43") (name "/VBAT+") (class "Default")
      (node (ref "F2") (pin "1") (pinfunction "1_1") (pintype "passive"))
      (node (ref "R1") (pin "1") (pinfunction "1_1") (pintype "passive"))
    )
    (net (code "44") (name "/VBAT-") (class "Default")
      (node (ref "F1") (pin "1") (pinfunction "1_1") (pintype "passive"))
      (node (ref "R2") (pin "2") (pinfunction "2_2") (pintype "passive"))
    )
    (net (code "45") (name "FUSED_VBAT+") (class "Default")
      (node (ref "F2") (pin "2") (pinfunction "2_2") (pintype "passive"))
    )
    (net (code "46") (name "FUSED_VBAT-") (class "Default")
      (node (ref "C1") (pin "2") (pinfunction "2_2") (pintype "passive"))
      (node (ref "C10") (pin "2") (pinfunction "2_2") (pintype "passive"))
      (node (ref "C11") (pin "2") (pinfunction "2_2") (pintype "passive"))
      (node (ref "C2") (pin "2") (pinfunction "2_2") (pintype "passive"))
      (node (ref "C3") (pin "2") (pinfunction "2_2") (pintype "passive"))
      (node (ref "C4") (pin "2") (pinfunction "2_2") (pintype "passive"))
      (node (ref "C5") (pin "2") (pinfunction "2_2") (pintype "passive"))
      (node (ref "C6") (pin "2") (pinfunction "2_2") (pintype "passive"))
      (node (ref "C7") (pin "2") (pinfunction "2_2") (pintype "passive"))
      (node (ref "C8") (pin "2") (pinfunction "2_2") (pintype "passive"))
      (node (ref "C9") (pin "2") (pinfunction "2_2") (pintype "passive"))
      (node (ref "F1") (pin "2") (pinfunction "2_2") (pintype "passive"))
    )
  )
)
